# mini-din-9.net
KiCad netlist of a schematic drawn in EAGLE
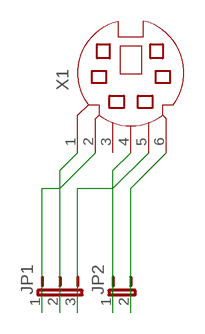
[diagram p0: schematic, sheet 1]

(export (version "E")
  (design (tool "Eeschema 10.0.6"))
  (components
    (comp (ref "JP1")
      (value "JP2E")
      (footprint "eagle-import:JP2")
      (libsource (lib "eagle-import") (part "JP2E"))
    )
    (comp (ref "JP2")
      (value "JP1E")
      (footprint "eagle-import:JP1")
      (libsource (lib "eagle-import") (part "JP1E"))
    )
    (comp (ref "X1")
      (value "MD06SS")
      (footprint "eagle-import:MDIN06SS")
      (libsource (lib "eagle-import") (part "MD06SS"))
    )
  )
  (nets
    (net (code "1") (name "Net-(JP1-Pad1)") (class "Default")
      (node (ref "JP1") (pin "1") (pinfunction "1_1") (pintype "passive"))
      (node (ref "X1") (pin "2") (pinfunction "2_2") (pintype "passive"))
    )
    (net (code "2") (name "Net-(JP1-Pad2)") (class "Default")
      (node (ref "JP1") (pin "2") (pinfunction "2_2") (pintype "passive"))
      (node (ref "X1") (pin "1") (pinfunction "1_1") (pintype "passive"))
    )
    (net (code "3") (name "Net-(JP1-Pad3)") (class "Default")
      (node (ref "JP1") (pin "3") (pinfunction "3_3") (pintype "passive"))
      (node (ref "X1") (pin "5") (pinfunction "5_5") (pintype "passive"))
    )
    (net (code "4") (name "Net-(JP2-Pad1)") (class "Default")
      (node (ref "JP2") (pin "1") (pinfunction "1_1") (pintype "passive"))
      (node (ref "X1") (pin "4") (pinfunction "4_4") (pintype "passive"))
    )
    (net (code "5") (name "Net-(JP2-Pad2)") (class "Default")
      (node (ref "JP2") (pin "2") (pinfunction "2_2") (pintype "passive"))
      (node (ref "X1") (pin "6") (pinfunction "6_6") (pintype "passive"))
    )
    (net (code "6") (name "unconnected-(X1-Pad3)") (class "Default")
      (node (ref "X1") (pin "3") (pinfunction "3_3") (pintype "passive"))
    )
  )
)
